# zmpt101b_-_3phase_din_v0_3.net
KiCad netlist of a schematic drawn in EAGLE
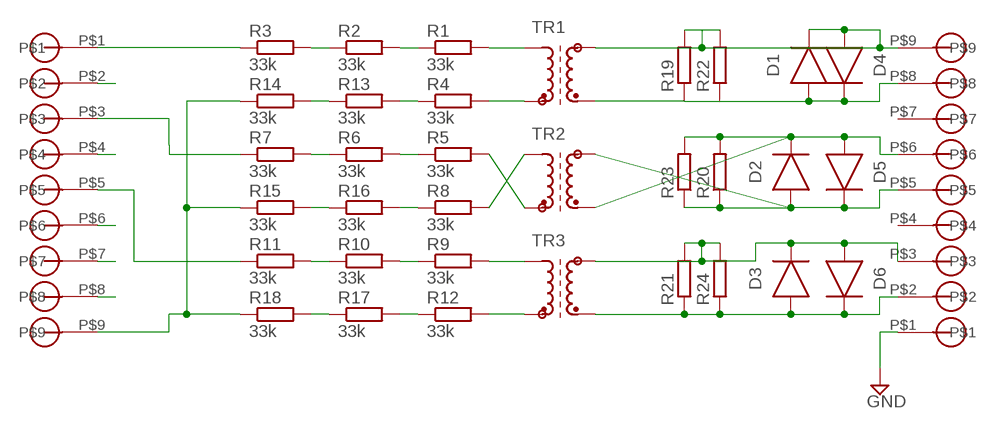
[diagram p0: schematic, sheet 1]

(export (version "E")
  (design (tool "Eeschema 10.0.6"))
  (components
    (comp (ref "D1")
      (value "DIODE_DO-219-AB(SOD123F)")
      (footprint "eagle-import:SODFL3718X115")
      (libsource (lib "eagle-import") (part "DIODEDO-219-AB(SOD123F)_"))
    )
    (comp (ref "D2")
      (value "DIODE_DO-219-AB(SOD123F)")
      (footprint "eagle-import:SODFL3718X115")
      (libsource (lib "eagle-import") (part "DIODEDO-219-AB(SOD123F)_"))
    )
    (comp (ref "D3")
      (value "DIODE_DO-219-AB(SOD123F)")
      (footprint "eagle-import:SODFL3718X115")
      (libsource (lib "eagle-import") (part "DIODEDO-219-AB(SOD123F)_"))
    )
    (comp (ref "D4")
      (value "DIODE_DO-219-AB(SOD123F)")
      (footprint "eagle-import:SODFL3718X115")
      (libsource (lib "eagle-import") (part "DIODEDO-219-AB(SOD123F)_"))
    )
    (comp (ref "D5")
      (value "DIODE_DO-219-AB(SOD123F)")
      (footprint "eagle-import:SODFL3718X115")
      (libsource (lib "eagle-import") (part "DIODEDO-219-AB(SOD123F)_"))
    )
    (comp (ref "D6")
      (value "DIODE_DO-219-AB(SOD123F)")
      (footprint "eagle-import:SODFL3718X115")
      (libsource (lib "eagle-import") (part "DIODEDO-219-AB(SOD123F)_"))
    )
    (comp (ref "R1")
      (value "33k")
      (footprint "eagle-import:R1206")
      (libsource (lib "eagle-import") (part "R-EU_R1206"))
    )
    (comp (ref "R2")
      (value "33k")
      (footprint "eagle-import:R1206")
      (libsource (lib "eagle-import") (part "R-EU_R1206"))
    )
    (comp (ref "R3")
      (value "33k")
      (footprint "eagle-import:R1206")
      (libsource (lib "eagle-import") (part "R-EU_R1206"))
    )
    (comp (ref "R4")
      (value "33k")
      (footprint "eagle-import:R1206")
      (libsource (lib "eagle-import") (part "R-EU_R1206"))
    )
    (comp (ref "R5")
      (value "33k")
      (footprint "eagle-import:R1206")
      (libsource (lib "eagle-import") (part "R-EU_R1206"))
    )
    (comp (ref "R6")
      (value "33k")
      (footprint "eagle-import:R1206")
      (libsource (lib "eagle-import") (part "R-EU_R1206"))
    )
    (comp (ref "R7")
      (value "33k")
      (footprint "eagle-import:R1206")
      (libsource (lib "eagle-import") (part "R-EU_R1206"))
    )
    (comp (ref "R8")
      (value "33k")
      (footprint "eagle-import:R1206")
      (libsource (lib "eagle-import") (part "R-EU_R1206"))
    )
    (comp (ref "R9")
      (value "33k")
      (footprint "eagle-import:R1206")
      (libsource (lib "eagle-import") (part "R-EU_R1206"))
    )
    (comp (ref "R10")
      (value "33k")
      (footprint "eagle-import:R1206")
      (libsource (lib "eagle-import") (part "R-EU_R1206"))
    )
    (comp (ref "R11")
      (value "33k")
      (footprint "eagle-import:R1206")
      (libsource (lib "eagle-import") (part "R-EU_R1206"))
    )
    (comp (ref "R12")
      (value "33k")
      (footprint "eagle-import:R1206")
      (libsource (lib "eagle-import") (part "R-EU_R1206"))
    )
    (comp (ref "R13")
      (value "33k")
      (footprint "eagle-import:R1206")
      (libsource (lib "eagle-import") (part "R-EU_R1206"))
    )
    (comp (ref "R14")
      (value "33k")
      (footprint "eagle-import:R1206")
      (libsource (lib "eagle-import") (part "R-EU_R1206"))
    )
    (comp (ref "R15")
      (value "33k")
      (footprint "eagle-import:R1206")
      (libsource (lib "eagle-import") (part "R-EU_R1206"))
    )
    (comp (ref "R16")
      (value "33k")
      (footprint "eagle-import:R1206")
      (libsource (lib "eagle-import") (part "R-EU_R1206"))
    )
    (comp (ref "R17")
      (value "33k")
      (footprint "eagle-import:R1206")
      (libsource (lib "eagle-import") (part "R-EU_R1206"))
    )
    (comp (ref "R18")
      (value "33k")
      (footprint "eagle-import:R1206")
      (libsource (lib "eagle-import") (part "R-EU_R1206"))
    )
    (comp (ref "R19")
      (value "110R")
      (footprint "eagle-import:R0603")
      (libsource (lib "eagle-import") (part "R-EU_R0603"))
    )
    (comp (ref "R20")
      (value "110R")
      (footprint "eagle-import:R0603")
      (libsource (lib "eagle-import") (part "R-EU_R0603"))
    )
    (comp (ref "R21")
      (value "110R")
      (footprint "eagle-import:R0603")
      (libsource (lib "eagle-import") (part "R-EU_R0603"))
    )
    (comp (ref "R22")
      (value "R-EU_0207/12")
      (footprint "eagle-import:0207_12")
      (libsource (lib "eagle-import") (part "R-EU_0207/12"))
    )
    (comp (ref "R23")
      (value "R-EU_0207/12")
      (footprint "eagle-import:0207_12")
      (libsource (lib "eagle-import") (part "R-EU_0207/12"))
    )
    (comp (ref "R24")
      (value "R-EU_0207/12")
      (footprint "eagle-import:0207_12")
      (libsource (lib "eagle-import") (part "R-EU_0207/12"))
    )
    (comp (ref "TR1")
      (value "ZMPT101B")
      (footprint "eagle-import:ZMPT101B")
      (libsource (lib "eagle-import") (part "ZMPT101B"))
    )
    (comp (ref "TR2")
      (value "ZMPT101B")
      (footprint "eagle-import:ZMPT101B")
      (libsource (lib "eagle-import") (part "ZMPT101B"))
    )
    (comp (ref "TR3")
      (value "ZMPT101B")
      (footprint "eagle-import:ZMPT101B")
      (libsource (lib "eagle-import") (part "ZMPT101B"))
    )
    (comp (ref "U$1")
      (value "5MMBLOCK_X9")
      (footprint "eagle-import:9_5.08")
      (libsource (lib "eagle-import") (part "5MMBLOCK_X9"))
    )
    (comp (ref "U$2")
      (value "5MMBLOCK_X9")
      (footprint "eagle-import:9_5.08")
      (libsource (lib "eagle-import") (part "5MMBLOCK_X9"))
    )
  )
  (nets
    (net (code "1") (name "/P$4") (class "Default")
      (node (ref "U$2") (pin "P$4") (pinfunction "P$4_P$4") (pintype "power_in"))
    )
    (net (code "2") (name "/P$7") (class "Default")
      (node (ref "U$2") (pin "P$7") (pinfunction "P$7_P$7") (pintype "power_in"))
    )
    (net (code "3") (name "GND") (class "Default")
      (node (ref "U$2") (pin "P$1") (pinfunction "P$1_P$1") (pintype "power_in"))
    )
    (net (code "4") (name "Net-(D1-A)") (class "Default")
      (node (ref "D1") (pin "2") (pinfunction "A_2") (pintype "passive"))
      (node (ref "D4") (pin "1") (pinfunction "C_1") (pintype "passive"))
      (node (ref "R19") (pin "1") (pinfunction "1_1") (pintype "passive"))
      (node (ref "R22") (pin "1") (pinfunction "1_1") (pintype "passive"))
      (node (ref "TR1") (pin "P$2") (pinfunction "E2_P$2") (pintype "passive"))
      (node (ref "U$2") (pin "P$8") (pinfunction "P$8_P$8") (pintype "power_in"))
    )
    (net (code "5") (name "Net-(D1-C)") (class "Default")
      (node (ref "D1") (pin "1") (pinfunction "C_1") (pintype "passive"))
      (node (ref "D4") (pin "2") (pinfunction "A_2") (pintype "passive"))
      (node (ref "R19") (pin "2") (pinfunction "2_2") (pintype "passive"))
      (node (ref "R22") (pin "2") (pinfunction "2_2") (pintype "passive"))
      (node (ref "TR1") (pin "P$1") (pinfunction "A2_P$1") (pintype "passive"))
      (node (ref "U$2") (pin "P$9") (pinfunction "P$9_P$9") (pintype "power_in"))
    )
    (net (code "6") (name "Net-(D2-A)") (class "Default")
      (node (ref "D2") (pin "2") (pinfunction "A_2") (pintype "passive"))
      (node (ref "D5") (pin "1") (pinfunction "C_1") (pintype "passive"))
      (node (ref "R20") (pin "1") (pinfunction "1_1") (pintype "passive"))
      (node (ref "R23") (pin "1") (pinfunction "1_1") (pintype "passive"))
      (node (ref "TR2") (pin "P$1") (pinfunction "A2_P$1") (pintype "passive"))
      (node (ref "U$2") (pin "P$5") (pinfunction "P$5_P$5") (pintype "power_in"))
    )
    (net (code "7") (name "Net-(D2-C)") (class "Default")
      (node (ref "D2") (pin "1") (pinfunction "C_1") (pintype "passive"))
      (node (ref "D5") (pin "2") (pinfunction "A_2") (pintype "passive"))
      (node (ref "R20") (pin "2") (pinfunction "2_2") (pintype "passive"))
      (node (ref "R23") (pin "2") (pinfunction "2_2") (pintype "passive"))
      (node (ref "TR2") (pin "P$2") (pinfunction "E2_P$2") (pintype "passive"))
      (node (ref "U$2") (pin "P$6") (pinfunction "P$6_P$6") (pintype "power_in"))
    )
    (net (code "8") (name "Net-(D3-A)") (class "Default")
      (node (ref "D3") (pin "2") (pinfunction "A_2") (pintype "passive"))
      (node (ref "D6") (pin "1") (pinfunction "C_1") (pintype "passive"))
      (node (ref "R21") (pin "1") (pinfunction "1_1") (pintype "passive"))
      (node (ref "R24") (pin "1") (pinfunction "1_1") (pintype "passive"))
      (node (ref "TR3") (pin "P$2") (pinfunction "E2_P$2") (pintype "passive"))
      (node (ref "U$2") (pin "P$2") (pinfunction "P$2_P$2") (pintype "power_in"))
    )
    (net (code "9") (name "Net-(D3-C)") (class "Default")
      (node (ref "D3") (pin "1") (pinfunction "C_1") (pintype "passive"))
      (node (ref "D6") (pin "2") (pinfunction "A_2") (pintype "passive"))
      (node (ref "R21") (pin "2") (pinfunction "2_2") (pintype "passive"))
      (node (ref "R24") (pin "2") (pinfunction "2_2") (pintype "passive"))
      (node (ref "TR3") (pin "P$1") (pinfunction "A2_P$1") (pintype "passive"))
      (node (ref "U$2") (pin "P$3") (pinfunction "P$3_P$3") (pintype "power_in"))
    )
    (net (code "10") (name "Net-(R1-Pad1)") (class "Default")
      (node (ref "R1") (pin "1") (pinfunction "1_1") (pintype "passive"))
      (node (ref "R2") (pin "2") (pinfunction "2_2") (pintype "passive"))
    )
    (net (code "11") (name "Net-(R2-Pad1)") (class "Default")
      (node (ref "R2") (pin "1") (pinfunction "1_1") (pintype "passive"))
      (node (ref "R3") (pin "2") (pinfunction "2_2") (pintype "passive"))
    )
    (net (code "12") (name "Net-(R3-Pad1)") (class "Default")
      (node (ref "R3") (pin "1") (pinfunction "1_1") (pintype "passive"))
      (node (ref "U$1") (pin "P$1") (pinfunction "P$1_P$1") (pintype "power_in"))
    )
    (net (code "13") (name "Net-(R5-Pad1)") (class "Default")
      (node (ref "R5") (pin "1") (pinfunction "1_1") (pintype "passive"))
      (node (ref "R6") (pin "2") (pinfunction "2_2") (pintype "passive"))
    )
    (net (code "14") (name "Net-(R6-Pad1)") (class "Default")
      (node (ref "R6") (pin "1") (pinfunction "1_1") (pintype "passive"))
      (node (ref "R7") (pin "2") (pinfunction "2_2") (pintype "passive"))
    )
    (net (code "15") (name "Net-(R7-Pad1)") (class "Default")
      (node (ref "R7") (pin "1") (pinfunction "1_1") (pintype "passive"))
      (node (ref "U$1") (pin "P$3") (pinfunction "P$3_P$3") (pintype "power_in"))
    )
    (net (code "16") (name "Net-(R10-Pad1)") (class "Default")
      (node (ref "R10") (pin "1") (pinfunction "1_1") (pintype "passive"))
      (node (ref "R11") (pin "2") (pinfunction "2_2") (pintype "passive"))
    )
    (net (code "17") (name "Net-(R10-Pad2)") (class "Default")
      (node (ref "R10") (pin "2") (pinfunction "2_2") (pintype "passive"))
      (node (ref "R9") (pin "1") (pinfunction "1_1") (pintype "passive"))
    )
    (net (code "18") (name "Net-(R11-Pad1)") (class "Default")
      (node (ref "R11") (pin "1") (pinfunction "1_1") (pintype "passive"))
      (node (ref "U$1") (pin "P$5") (pinfunction "P$5_P$5") (pintype "power_in"))
    )
    (net (code "19") (name "Net-(R12-Pad1)") (class "Default")
      (node (ref "R12") (pin "1") (pinfunction "1_1") (pintype "passive"))
      (node (ref "R17") (pin "2") (pinfunction "2_2") (pintype "passive"))
    )
    (net (code "20") (name "Net-(R13-Pad1)") (class "Default")
      (node (ref "R13") (pin "1") (pinfunction "1_1") (pintype "passive"))
      (node (ref "R14") (pin "2") (pinfunction "2_2") (pintype "passive"))
    )
    (net (code "21") (name "Net-(R13-Pad2)") (class "Default")
      (node (ref "R13") (pin "2") (pinfunction "2_2") (pintype "passive"))
      (node (ref "R4") (pin "1") (pinfunction "1_1") (pintype "passive"))
    )
    (net (code "22") (name "Net-(R14-Pad1)") (class "Default")
      (node (ref "R14") (pin "1") (pinfunction "1_1") (pintype "passive"))
      (node (ref "R15") (pin "1") (pinfunction "1_1") (pintype "passive"))
      (node (ref "R18") (pin "1") (pinfunction "1_1") (pintype "passive"))
      (node (ref "U$1") (pin "P$9") (pinfunction "P$9_P$9") (pintype "power_in"))
    )
    (net (code "23") (name "Net-(R15-Pad2)") (class "Default")
      (node (ref "R15") (pin "2") (pinfunction "2_2") (pintype "passive"))
      (node (ref "R16") (pin "1") (pinfunction "1_1") (pintype "passive"))
    )
    (net (code "24") (name "Net-(R16-Pad2)") (class "Default")
      (node (ref "R16") (pin "2") (pinfunction "2_2") (pintype "passive"))
      (node (ref "R8") (pin "1") (pinfunction "1_1") (pintype "passive"))
    )
    (net (code "25") (name "Net-(R17-Pad1)") (class "Default")
      (node (ref "R17") (pin "1") (pinfunction "1_1") (pintype "passive"))
      (node (ref "R18") (pin "2") (pinfunction "2_2") (pintype "passive"))
    )
    (net (code "26") (name "Net-(TR1-A1)") (class "Default")
      (node (ref "R1") (pin "2") (pinfunction "2_2") (pintype "passive"))
      (node (ref "TR1") (pin "P$4") (pinfunction "A1_P$4") (pintype "passive"))
    )
    (net (code "27") (name "Net-(TR1-E1)") (class "Default")
      (node (ref "R4") (pin "2") (pinfunction "2_2") (pintype "passive"))
      (node (ref "TR1") (pin "P$3") (pinfunction "E1_P$3") (pintype "passive"))
    )
    (net (code "28") (name "Net-(TR2-A1)") (class "Default")
      (node (ref "R8") (pin "2") (pinfunction "2_2") (pintype "passive"))
      (node (ref "TR2") (pin "P$4") (pinfunction "A1_P$4") (pintype "passive"))
    )
    (net (code "29") (name "Net-(TR2-E1)") (class "Default")
      (node (ref "R5") (pin "2") (pinfunction "2_2") (pintype "passive"))
      (node (ref "TR2") (pin "P$3") (pinfunction "E1_P$3") (pintype "passive"))
    )
    (net (code "30") (name "Net-(TR3-A1)") (class "Default")
      (node (ref "R9") (pin "2") (pinfunction "2_2") (pintype "passive"))
      (node (ref "TR3") (pin "P$4") (pinfunction "A1_P$4") (pintype "passive"))
    )
    (net (code "31") (name "Net-(TR3-E1)") (class "Default")
      (node (ref "R12") (pin "2") (pinfunction "2_2") (pintype "passive"))
      (node (ref "TR3") (pin "P$3") (pinfunction "E1_P$3") (pintype "passive"))
    )
    (net (code "32") (name "unconnected-(U$1-PadP$2)") (class "Default")
      (node (ref "U$1") (pin "P$2") (pinfunction "P$2_P$2") (pintype "power_in"))
    )
    (net (code "33") (name "unconnected-(U$1-PadP$4)") (class "Default")
      (node (ref "U$1") (pin "P$4") (pinfunction "P$4_P$4") (pintype "power_in"))
    )
    (net (code "34") (name "unconnected-(U$1-PadP$6)") (class "Default")
      (node (ref "U$1") (pin "P$6") (pinfunction "P$6_P$6") (pintype "power_in"))
    )
    (net (code "35") (name "unconnected-(U$1-PadP$7)") (class "Default")
      (node (ref "U$1") (pin "P$7") (pinfunction "P$7_P$7") (pintype "power_in"))
    )
    (net (code "36") (name "unconnected-(U$1-PadP$8)") (class "Default")
      (node (ref "U$1") (pin "P$8") (pinfunction "P$8_P$8") (pintype "power_in"))
    )
  )
)
